# 780-00020_rev_2_pg1_Two_Axis_Stepper_Dri.net
KiCad netlist of a schematic drawn in Altium Designer
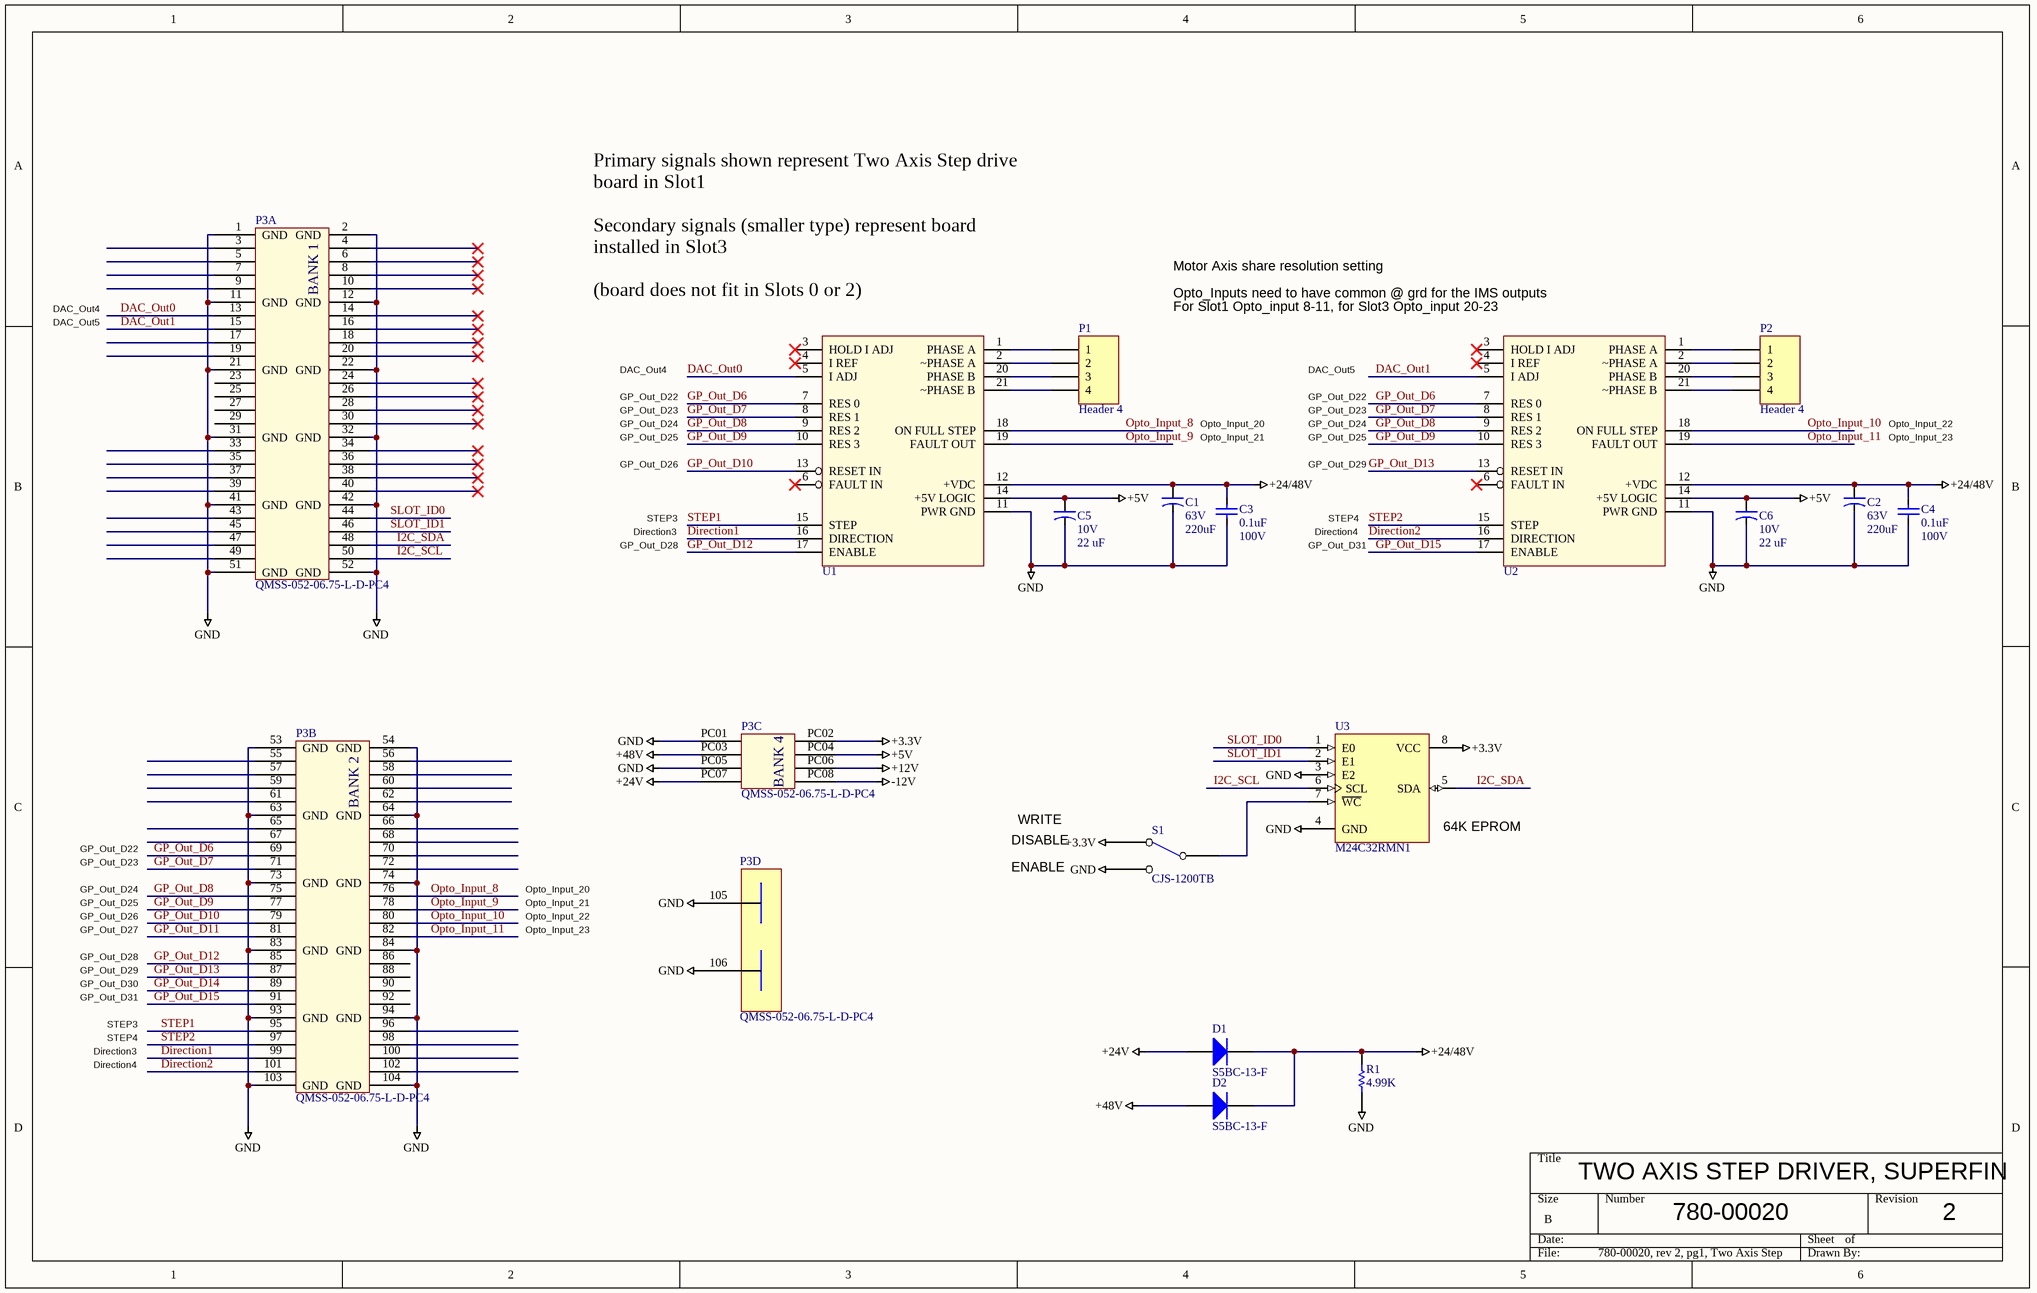
[diagram p0: 780-00020, rev 2, pg1, Two Axis Stepper Driver.SchDoc]

(export (version "E")
  (design (tool "Eeschema 10.0.6"))
  (components
    (comp (ref "C1")
      (value "63V")
      (footprint "CAP 220uF 63V")
      (description "CAP 220UF 63V ELECT MVH SMD")
      (fields (field (name "MANUFACTURER") "United Chemi-Con") (field (name "ALTIUM_VALUE") "220uF"))
      (libsource (lib "Richs Schematic Components") (part "Cap 220uF, 63V"))
    )
    (comp (ref "C2")
      (value "63V")
      (footprint "CAP 220uF 63V")
      (description "CAP 220UF 63V ELECT MVH SMD")
      (fields (field (name "MANUFACTURER") "United Chemi-Con") (field (name "ALTIUM_VALUE") "220uF"))
      (libsource (lib "Richs Schematic Components") (part "Cap 220uF, 63V"))
    )
    (comp (ref "C3")
      (value "100V")
      (footprint "SMD_0805")
      (description "Capacitor")
      (fields (field (name "MANUFACTURER") "TDK") (field (name "ALTIUM_VALUE") "0.1uF"))
      (libsource (lib "Richs Schematic Components") (part "Cap SMD"))
    )
    (comp (ref "C4")
      (value "100V")
      (footprint "SMD_0805")
      (description "Capacitor")
      (fields (field (name "MANUFACTURER") "TDK") (field (name "ALTIUM_VALUE") "0.1uF"))
      (libsource (lib "Richs Schematic Components") (part "Cap SMD"))
    )
    (comp (ref "C5")
      (value "10V")
      (footprint "SMD_CAP_3216")
      (description "outline 3.2mm x 1.6mm")
      (fields (field (name "MANUFACTURER") "AVX") (field (name "ALTIUM_VALUE") "22 uF"))
      (libsource (lib "Richs Schematic Components") (part "Cap Tant 16V"))
    )
    (comp (ref "C6")
      (value "10V")
      (footprint "SMD_CAP_3216")
      (description "outline 3.2mm x 1.6mm")
      (fields (field (name "MANUFACTURER") "AVX") (field (name "ALTIUM_VALUE") "22 uF"))
      (libsource (lib "Richs Schematic Components") (part "Cap Tant 16V"))
    )
    (comp (ref "D1")
      (value "S5BC-13-F")
      (footprint "SMC")
      (description "RECTIFIER GPP SMD 100V 5A SMC")
      (fields (field (name "MANUFACTURER") "Diodes Inc"))
      (libsource (lib "Miscellaneous Devices") (part "Diode"))
    )
    (comp (ref "D2")
      (value "S5BC-13-F")
      (footprint "SMC")
      (description "RECTIFIER GPP SMD 100V 5A SMC")
      (fields (field (name "MANUFACTURER") "Diodes Inc"))
      (libsource (lib "Miscellaneous Devices") (part "Diode"))
    )
    (comp (ref "P1")
      (value "Header 4")
      (footprint "HDR1X4 for IDC")
      (description "Header, 4-Pin")
      (libsource (lib "Richs Schematic Components") (part "Header 4"))
    )
    (comp (ref "P2")
      (value "Header 4")
      (footprint "HDR1X4 for IDC")
      (description "Header, 4-Pin")
      (libsource (lib "Richs Schematic Components") (part "Header 4"))
    )
    (comp (ref "P3")
      (value "QMSS-052-06.75-L-D-PC4")
      (footprint "QMS SMD PWR PINS - 104PIN")
      (description "SAMTEC QMSS W/PWR PINS")
      (fields (field (name "MANUFACTURER") "SAMTEC"))
      (libsource (lib "Richs Schematic Components") (part "QMSS-PC4-104 pin"))
    )
    (comp (ref "R1")
      (value "4.99K")
      (footprint "SMD_0805")
      (description "Resistor 0805")
      (fields (field (name "MANUFACTURER") "Vishay/Dale") (field (name "Comment") "Res 0805"))
      (libsource (lib "Richs Schematic Components") (part "Res SMD"))
    )
    (comp (ref "S1")
      (value "CJS-1200TB")
      (footprint "CAS-120B")
      (fields (field (name "MANUFACTURER") "Copal Electronics"))
      (libsource (lib "JON_1_Library") (part "SW_SPDT_DOUG"))
    )
    (comp (ref "U1")
      (value "IM481H Plus")
      (footprint "IM481H Vertical")
      (description "Hybrid stepper motor driver")
      (libsource (lib "Richs Schematic Components") (part "IM481H Plus"))
    )
    (comp (ref "U2")
      (value "IM481H Plus")
      (footprint "IM481H Vertical")
      (description "Hybrid stepper motor driver")
      (libsource (lib "Richs Schematic Components") (part "IM481H Plus"))
    )
    (comp (ref "U3")
      (value "M24C32RMN1")
      (footprint "SOP8_N")
      (description "32 Kbit Serial I²C Bus EEPROM")
      (libsource (lib "ST Memory EEPROM Serial") (part "M24C32RMN1"))
    )
  )
  (nets
    (net (code "1") (name "+3.3V") (class "Default")
      (node (ref "P3") (pin "PC02") (pinfunction "PC02_PC02") (pintype "passive"))
      (node (ref "S1") (pin "3") (pinfunction "NC_3") (pintype "passive"))
      (node (ref "U3") (pin "8") (pinfunction "VCC_8") (pintype "power_in"))
    )
    (net (code "2") (name "+5V") (class "Default")
      (node (ref "C5") (pin "1") (pinfunction "1_1") (pintype "passive"))
      (node (ref "C6") (pin "1") (pinfunction "1_1") (pintype "passive"))
      (node (ref "P3") (pin "PC04") (pinfunction "PC04_PC04") (pintype "passive"))
      (node (ref "U1") (pin "14") (pinfunction "+5V_LOGIC_14") (pintype "passive"))
      (node (ref "U2") (pin "14") (pinfunction "+5V_LOGIC_14") (pintype "passive"))
    )
    (net (code "3") (name "+12V") (class "Default")
      (node (ref "P3") (pin "PC06") (pinfunction "PC06_PC06") (pintype "passive"))
    )
    (net (code "4") (name "+24V") (class "Default")
      (node (ref "D1") (pin "1") (pinfunction "A_1") (pintype "passive"))
      (node (ref "P3") (pin "PC07") (pinfunction "PC07_PC07") (pintype "passive"))
    )
    (net (code "5") (name "+24{slash}48V") (class "Default")
      (node (ref "C1") (pin "1") (pinfunction "1_1") (pintype "passive"))
      (node (ref "C2") (pin "1") (pinfunction "1_1") (pintype "passive"))
      (node (ref "C3") (pin "2") (pinfunction "2_2") (pintype "passive"))
      (node (ref "C4") (pin "2") (pinfunction "2_2") (pintype "passive"))
      (node (ref "D1") (pin "2") (pinfunction "K_2") (pintype "passive"))
      (node (ref "D2") (pin "2") (pinfunction "K_2") (pintype "passive"))
      (node (ref "R1") (pin "2") (pinfunction "2_2") (pintype "passive"))
      (node (ref "U1") (pin "12") (pinfunction "+VDC_12") (pintype "passive"))
      (node (ref "U2") (pin "12") (pinfunction "+VDC_12") (pintype "passive"))
    )
    (net (code "6") (name "+48V") (class "Default")
      (node (ref "D2") (pin "1") (pinfunction "A_1") (pintype "passive"))
      (node (ref "P3") (pin "PC03") (pinfunction "PC03_PC03") (pintype "passive"))
    )
    (net (code "7") (name "-12V") (class "Default")
      (node (ref "P3") (pin "PC08") (pinfunction "PC08_PC08") (pintype "passive"))
    )
    (net (code "8") (name "/DAC_Out0") (class "Default")
      (node (ref "P3") (pin "13") (pinfunction "13_13") (pintype "passive"))
      (node (ref "U1") (pin "5") (pinfunction "I_ADJ_5") (pintype "passive"))
    )
    (net (code "9") (name "/DAC_Out1") (class "Default")
      (node (ref "P3") (pin "15") (pinfunction "15_15") (pintype "passive"))
      (node (ref "U2") (pin "5") (pinfunction "I_ADJ_5") (pintype "passive"))
    )
    (net (code "10") (name "/Direction1") (class "Default")
      (node (ref "P3") (pin "99") (pinfunction "99_99") (pintype "passive"))
      (node (ref "U1") (pin "16") (pinfunction "DIRECTION_16") (pintype "passive"))
    )
    (net (code "11") (name "/Direction2") (class "Default")
      (node (ref "P3") (pin "101") (pinfunction "101_101") (pintype "passive"))
      (node (ref "U2") (pin "16") (pinfunction "DIRECTION_16") (pintype "passive"))
    )
    (net (code "12") (name "/GP_Out_D6") (class "Default")
      (node (ref "P3") (pin "69") (pinfunction "69_69") (pintype "passive"))
      (node (ref "U1") (pin "7") (pinfunction "RES_0_7") (pintype "passive"))
      (node (ref "U2") (pin "7") (pinfunction "RES_0_7") (pintype "passive"))
    )
    (net (code "13") (name "/GP_Out_D7") (class "Default")
      (node (ref "P3") (pin "71") (pinfunction "71_71") (pintype "passive"))
      (node (ref "U1") (pin "8") (pinfunction "RES_1_8") (pintype "passive"))
      (node (ref "U2") (pin "8") (pinfunction "RES_1_8") (pintype "passive"))
    )
    (net (code "14") (name "/GP_Out_D8") (class "Default")
      (node (ref "P3") (pin "75") (pinfunction "75_75") (pintype "passive"))
      (node (ref "U1") (pin "9") (pinfunction "RES_2_9") (pintype "passive"))
      (node (ref "U2") (pin "9") (pinfunction "RES_2_9") (pintype "passive"))
    )
    (net (code "15") (name "/GP_Out_D9") (class "Default")
      (node (ref "P3") (pin "77") (pinfunction "77_77") (pintype "passive"))
      (node (ref "U1") (pin "10") (pinfunction "RES_3_10") (pintype "passive"))
      (node (ref "U2") (pin "10") (pinfunction "RES_3_10") (pintype "passive"))
    )
    (net (code "16") (name "/GP_Out_D10") (class "Default")
      (node (ref "P3") (pin "79") (pinfunction "79_79") (pintype "passive"))
      (node (ref "U1") (pin "13") (pinfunction "RESET_IN_13") (pintype "passive"))
    )
    (net (code "17") (name "/GP_Out_D11") (class "Default")
      (node (ref "P3") (pin "81") (pinfunction "81_81") (pintype "passive"))
    )
    (net (code "18") (name "/GP_Out_D12") (class "Default")
      (node (ref "P3") (pin "85") (pinfunction "85_85") (pintype "passive"))
      (node (ref "U1") (pin "17") (pinfunction "ENABLE_17") (pintype "passive"))
    )
    (net (code "19") (name "/GP_Out_D13") (class "Default")
      (node (ref "P3") (pin "87") (pinfunction "87_87") (pintype "passive"))
      (node (ref "U2") (pin "13") (pinfunction "RESET_IN_13") (pintype "passive"))
    )
    (net (code "20") (name "/GP_Out_D14") (class "Default")
      (node (ref "P3") (pin "89") (pinfunction "89_89") (pintype "passive"))
    )
    (net (code "21") (name "/GP_Out_D15") (class "Default")
      (node (ref "P3") (pin "91") (pinfunction "91_91") (pintype "passive"))
      (node (ref "U2") (pin "17") (pinfunction "ENABLE_17") (pintype "passive"))
    )
    (net (code "22") (name "/I2C_SCL") (class "Default")
      (node (ref "P3") (pin "50") (pinfunction "50_50") (pintype "passive"))
      (node (ref "U3") (pin "6") (pinfunction "SCL_6") (pintype "input"))
    )
    (net (code "23") (name "/I2C_SDA") (class "Default")
      (node (ref "P3") (pin "48") (pinfunction "48_48") (pintype "passive"))
      (node (ref "U3") (pin "5") (pinfunction "SDA_5") (pintype "bidirectional"))
    )
    (net (code "24") (name "/Opto_Input_8") (class "Default")
      (node (ref "P3") (pin "76") (pinfunction "76_76") (pintype "passive"))
      (node (ref "U1") (pin "18") (pinfunction "ON_FULL_STEP_18") (pintype "passive"))
    )
    (net (code "25") (name "/Opto_Input_9") (class "Default")
      (node (ref "P3") (pin "78") (pinfunction "78_78") (pintype "passive"))
      (node (ref "U1") (pin "19") (pinfunction "FAULT_OUT_19") (pintype "passive"))
    )
    (net (code "26") (name "/Opto_Input_10") (class "Default")
      (node (ref "P3") (pin "80") (pinfunction "80_80") (pintype "passive"))
      (node (ref "U2") (pin "18") (pinfunction "ON_FULL_STEP_18") (pintype "passive"))
    )
    (net (code "27") (name "/Opto_Input_11") (class "Default")
      (node (ref "P3") (pin "82") (pinfunction "82_82") (pintype "passive"))
      (node (ref "U2") (pin "19") (pinfunction "FAULT_OUT_19") (pintype "passive"))
    )
    (net (code "28") (name "/SLOT_ID0") (class "Default")
      (node (ref "P3") (pin "44") (pinfunction "44_44") (pintype "passive"))
      (node (ref "U3") (pin "1") (pinfunction "E0_1") (pintype "input"))
    )
    (net (code "29") (name "/SLOT_ID1") (class "Default")
      (node (ref "P3") (pin "46") (pinfunction "46_46") (pintype "passive"))
      (node (ref "U3") (pin "2") (pinfunction "E1_2") (pintype "input"))
    )
    (net (code "30") (name "/STEP1") (class "Default")
      (node (ref "P3") (pin "95") (pinfunction "95_95") (pintype "passive"))
      (node (ref "U1") (pin "15") (pinfunction "STEP_15") (pintype "passive"))
    )
    (net (code "31") (name "/STEP2") (class "Default")
      (node (ref "P3") (pin "97") (pinfunction "97_97") (pintype "passive"))
      (node (ref "U2") (pin "15") (pinfunction "STEP_15") (pintype "passive"))
    )
    (net (code "32") (name "GND") (class "Default")
      (node (ref "C1") (pin "2") (pinfunction "2_2") (pintype "passive"))
      (node (ref "C2") (pin "2") (pinfunction "2_2") (pintype "passive"))
      (node (ref "C3") (pin "1") (pinfunction "1_1") (pintype "passive"))
      (node (ref "C4") (pin "1") (pinfunction "1_1") (pintype "passive"))
      (node (ref "C5") (pin "2") (pinfunction "2_2") (pintype "passive"))
      (node (ref "C6") (pin "2") (pinfunction "2_2") (pintype "passive"))
      (node (ref "P3") (pin "1") (pinfunction "GND_1") (pintype "passive"))
      (node (ref "P3") (pin "103") (pinfunction "GND_103") (pintype "passive"))
      (node (ref "P3") (pin "104") (pinfunction "GND_104") (pintype "passive"))
      (node (ref "P3") (pin "105") (pinfunction "GND_105") (pintype "passive"))
      (node (ref "P3") (pin "106") (pinfunction "GND_106") (pintype "passive"))
      (node (ref "P3") (pin "11") (pinfunction "GND_11") (pintype "passive"))
      (node (ref "P3") (pin "12") (pinfunction "GND_12") (pintype "passive"))
      (node (ref "P3") (pin "2") (pinfunction "GND_2") (pintype "passive"))
      (node (ref "P3") (pin "21") (pinfunction "GND_21") (pintype "passive"))
      (node (ref "P3") (pin "22") (pinfunction "GND_22") (pintype "passive"))
      (node (ref "P3") (pin "31") (pinfunction "GND_31") (pintype "passive"))
      (node (ref "P3") (pin "32") (pinfunction "GND_32") (pintype "passive"))
      (node (ref "P3") (pin "41") (pinfunction "GND_41") (pintype "passive"))
      (node (ref "P3") (pin "42") (pinfunction "GND_42") (pintype "passive"))
      (node (ref "P3") (pin "51") (pinfunction "GND_51") (pintype "passive"))
      (node (ref "P3") (pin "52") (pinfunction "GND_52") (pintype "passive"))
      (node (ref "P3") (pin "53") (pinfunction "GND_53") (pintype "passive"))
      (node (ref "P3") (pin "54") (pinfunction "GND_54") (pintype "passive"))
      (node (ref "P3") (pin "63") (pinfunction "GND_63") (pintype "passive"))
      (node (ref "P3") (pin "64") (pinfunction "GND_64") (pintype "passive"))
      (node (ref "P3") (pin "73") (pinfunction "GND_73") (pintype "passive"))
      (node (ref "P3") (pin "74") (pinfunction "GND_74") (pintype "passive"))
      (node (ref "P3") (pin "83") (pinfunction "GND_83") (pintype "passive"))
      (node (ref "P3") (pin "84") (pinfunction "GND_84") (pintype "passive"))
      (node (ref "P3") (pin "93") (pinfunction "GND_93") (pintype "passive"))
      (node (ref "P3") (pin "94") (pinfunction "GND_94") (pintype "passive"))
      (node (ref "P3") (pin "PC01") (pinfunction "PC01_PC01") (pintype "passive"))
      (node (ref "P3") (pin "PC05") (pinfunction "PC05_PC05") (pintype "passive"))
      (node (ref "R1") (pin "1") (pinfunction "1_1") (pintype "passive"))
      (node (ref "S1") (pin "1") (pinfunction "NO_1") (pintype "passive"))
      (node (ref "U1") (pin "11") (pinfunction "PWR_GND_11") (pintype "passive"))
      (node (ref "U2") (pin "11") (pinfunction "PWR_GND_11") (pintype "passive"))
      (node (ref "U3") (pin "3") (pinfunction "E2_3") (pintype "input"))
      (node (ref "U3") (pin "4") (pinfunction "GND_4") (pintype "power_in"))
    )
    (net (code "33") (name "Net-(S1-COM)") (class "Default")
      (node (ref "S1") (pin "2") (pinfunction "COM_2") (pintype "passive"))
      (node (ref "U3") (pin "7") (pinfunction "~{WC}_7") (pintype "input"))
    )
    (net (code "34") (name "Net-(U1-PHASE_A)") (class "Default")
      (node (ref "P1") (pin "1") (pinfunction "1_1") (pintype "passive"))
      (node (ref "U1") (pin "1") (pinfunction "PHASE_A_1") (pintype "passive"))
    )
    (net (code "35") (name "Net-(U1-PHASE_B)") (class "Default")
      (node (ref "P1") (pin "3") (pinfunction "3_3") (pintype "passive"))
      (node (ref "U1") (pin "20") (pinfunction "PHASE_B_20") (pintype "passive"))
    )
    (net (code "36") (name "Net-(U1-~PHASE_A)") (class "Default")
      (node (ref "P1") (pin "2") (pinfunction "2_2") (pintype "passive"))
      (node (ref "U1") (pin "2") (pinfunction "~PHASE_A_2") (pintype "passive"))
    )
    (net (code "37") (name "Net-(U1-~PHASE_B)") (class "Default")
      (node (ref "P1") (pin "4") (pinfunction "4_4") (pintype "passive"))
      (node (ref "U1") (pin "21") (pinfunction "~PHASE_B_21") (pintype "passive"))
    )
    (net (code "38") (name "Net-(U2-PHASE_A)") (class "Default")
      (node (ref "P2") (pin "1") (pinfunction "1_1") (pintype "passive"))
      (node (ref "U2") (pin "1") (pinfunction "PHASE_A_1") (pintype "passive"))
    )
    (net (code "39") (name "Net-(U2-PHASE_B)") (class "Default")
      (node (ref "P2") (pin "3") (pinfunction "3_3") (pintype "passive"))
      (node (ref "U2") (pin "20") (pinfunction "PHASE_B_20") (pintype "passive"))
    )
    (net (code "40") (name "Net-(U2-~PHASE_A)") (class "Default")
      (node (ref "P2") (pin "2") (pinfunction "2_2") (pintype "passive"))
      (node (ref "U2") (pin "2") (pinfunction "~PHASE_A_2") (pintype "passive"))
    )
    (net (code "41") (name "Net-(U2-~PHASE_B)") (class "Default")
      (node (ref "P2") (pin "4") (pinfunction "4_4") (pintype "passive"))
      (node (ref "U2") (pin "21") (pinfunction "~PHASE_B_21") (pintype "passive"))
    )
    (net (code "42") (name "unconnected-(P3-Pad3)") (class "Default")
      (node (ref "P3") (pin "3") (pinfunction "3_3") (pintype "passive"))
    )
    (net (code "43") (name "unconnected-(P3-Pad4)") (class "Default")
      (node (ref "P3") (pin "4") (pinfunction "4_4") (pintype "passive+no_connect"))
    )
    (net (code "44") (name "unconnected-(P3-Pad5)") (class "Default")
      (node (ref "P3") (pin "5") (pinfunction "5_5") (pintype "passive"))
    )
    (net (code "45") (name "unconnected-(P3-Pad6)") (class "Default")
      (node (ref "P3") (pin "6") (pinfunction "6_6") (pintype "passive+no_connect"))
    )
    (net (code "46") (name "unconnected-(P3-Pad7)") (class "Default")
      (node (ref "P3") (pin "7") (pinfunction "7_7") (pintype "passive"))
    )
    (net (code "47") (name "unconnected-(P3-Pad8)") (class "Default")
      (node (ref "P3") (pin "8") (pinfunction "8_8") (pintype "passive+no_connect"))
    )
    (net (code "48") (name "unconnected-(P3-Pad9)") (class "Default")
      (node (ref "P3") (pin "9") (pinfunction "9_9") (pintype "passive"))
    )
    (net (code "49") (name "unconnected-(P3-Pad10)") (class "Default")
      (node (ref "P3") (pin "10") (pinfunction "10_10") (pintype "passive+no_connect"))
    )
    (net (code "50") (name "unconnected-(P3-Pad14)") (class "Default")
      (node (ref "P3") (pin "14") (pinfunction "14_14") (pintype "passive+no_connect"))
    )
    (net (code "51") (name "unconnected-(P3-Pad16)") (class "Default")
      (node (ref "P3") (pin "16") (pinfunction "16_16") (pintype "passive+no_connect"))
    )
    (net (code "52") (name "unconnected-(P3-Pad17)") (class "Default")
      (node (ref "P3") (pin "17") (pinfunction "17_17") (pintype "passive"))
    )
    (net (code "53") (name "unconnected-(P3-Pad18)") (class "Default")
      (node (ref "P3") (pin "18") (pinfunction "18_18") (pintype "passive+no_connect"))
    )
    (net (code "54") (name "unconnected-(P3-Pad19)") (class "Default")
      (node (ref "P3") (pin "19") (pinfunction "19_19") (pintype "passive"))
    )
    (net (code "55") (name "unconnected-(P3-Pad20)") (class "Default")
      (node (ref "P3") (pin "20") (pinfunction "20_20") (pintype "passive+no_connect"))
    )
    (net (code "56") (name "unconnected-(P3-Pad23)") (class "Default")
      (node (ref "P3") (pin "23") (pinfunction "23_23") (pintype "passive"))
    )
    (net (code "57") (name "unconnected-(P3-Pad24)") (class "Default")
      (node (ref "P3") (pin "24") (pinfunction "24_24") (pintype "passive+no_connect"))
    )
    (net (code "58") (name "unconnected-(P3-Pad25)") (class "Default")
      (node (ref "P3") (pin "25") (pinfunction "25_25") (pintype "passive"))
    )
    (net (code "59") (name "unconnected-(P3-Pad26)") (class "Default")
      (node (ref "P3") (pin "26") (pinfunction "26_26") (pintype "passive+no_connect"))
    )
    (net (code "60") (name "unconnected-(P3-Pad27)") (class "Default")
      (node (ref "P3") (pin "27") (pinfunction "27_27") (pintype "passive"))
    )
    (net (code "61") (name "unconnected-(P3-Pad28)") (class "Default")
      (node (ref "P3") (pin "28") (pinfunction "28_28") (pintype "passive+no_connect"))
    )
    (net (code "62") (name "unconnected-(P3-Pad29)") (class "Default")
      (node (ref "P3") (pin "29") (pinfunction "29_29") (pintype "passive"))
    )
    (net (code "63") (name "unconnected-(P3-Pad30)") (class "Default")
      (node (ref "P3") (pin "30") (pinfunction "30_30") (pintype "passive+no_connect"))
    )
    (net (code "64") (name "unconnected-(P3-Pad33)") (class "Default")
      (node (ref "P3") (pin "33") (pinfunction "33_33") (pintype "passive"))
    )
    (net (code "65") (name "unconnected-(P3-Pad34)") (class "Default")
      (node (ref "P3") (pin "34") (pinfunction "34_34") (pintype "passive+no_connect"))
    )
    (net (code "66") (name "unconnected-(P3-Pad35)") (class "Default")
      (node (ref "P3") (pin "35") (pinfunction "35_35") (pintype "passive"))
    )
    (net (code "67") (name "unconnected-(P3-Pad36)") (class "Default")
      (node (ref "P3") (pin "36") (pinfunction "36_36") (pintype "passive+no_connect"))
    )
    (net (code "68") (name "unconnected-(P3-Pad37)") (class "Default")
      (node (ref "P3") (pin "37") (pinfunction "37_37") (pintype "passive"))
    )
    (net (code "69") (name "unconnected-(P3-Pad38)") (class "Default")
      (node (ref "P3") (pin "38") (pinfunction "38_38") (pintype "passive+no_connect"))
    )
    (net (code "70") (name "unconnected-(P3-Pad39)") (class "Default")
      (node (ref "P3") (pin "39") (pinfunction "39_39") (pintype "passive"))
    )
    (net (code "71") (name "unconnected-(P3-Pad40)") (class "Default")
      (node (ref "P3") (pin "40") (pinfunction "40_40") (pintype "passive+no_connect"))
    )
    (net (code "72") (name "unconnected-(P3-Pad43)") (class "Default")
      (node (ref "P3") (pin "43") (pinfunction "43_43") (pintype "passive"))
    )
    (net (code "73") (name "unconnected-(P3-Pad45)") (class "Default")
      (node (ref "P3") (pin "45") (pinfunction "45_45") (pintype "passive"))
    )
    (net (code "74") (name "unconnected-(P3-Pad47)") (class "Default")
      (node (ref "P3") (pin "47") (pinfunction "47_47") (pintype "passive"))
    )
    (net (code "75") (name "unconnected-(P3-Pad49)") (class "Default")
      (node (ref "P3") (pin "49") (pinfunction "49_49") (pintype "passive"))
    )
    (net (code "76") (name "unconnected-(P3-Pad55)") (class "Default")
      (node (ref "P3") (pin "55") (pinfunction "55_55") (pintype "passive"))
    )
    (net (code "77") (name "unconnected-(P3-Pad56)") (class "Default")
      (node (ref "P3") (pin "56") (pinfunction "56_56") (pintype "passive"))
    )
    (net (code "78") (name "unconnected-(P3-Pad57)") (class "Default")
      (node (ref "P3") (pin "57") (pinfunction "57_57") (pintype "passive"))
    )
    (net (code "79") (name "unconnected-(P3-Pad58)") (class "Default")
      (node (ref "P3") (pin "58") (pinfunction "58_58") (pintype "passive"))
    )
    (net (code "80") (name "unconnected-(P3-Pad59)") (class "Default")
      (node (ref "P3") (pin "59") (pinfunction "59_59") (pintype "passive"))
    )
    (net (code "81") (name "unconnected-(P3-Pad60)") (class "Default")
      (node (ref "P3") (pin "60") (pinfunction "60_60") (pintype "passive"))
    )
    (net (code "82") (name "unconnected-(P3-Pad61)") (class "Default")
      (node (ref "P3") (pin "61") (pinfunction "61_61") (pintype "passive"))
    )
    (net (code "83") (name "unconnected-(P3-Pad62)") (class "Default")
      (node (ref "P3") (pin "62") (pinfunction "62_62") (pintype "passive"))
    )
    (net (code "84") (name "unconnected-(P3-Pad65)") (class "Default")
      (node (ref "P3") (pin "65") (pinfunction "65_65") (pintype "passive"))
    )
    (net (code "85") (name "unconnected-(P3-Pad66)") (class "Default")
      (node (ref "P3") (pin "66") (pinfunction "66_66") (pintype "passive"))
    )
    (net (code "86") (name "unconnected-(P3-Pad67)") (class "Default")
      (node (ref "P3") (pin "67") (pinfunction "67_67") (pintype "passive"))
    )
    (net (code "87") (name "unconnected-(P3-Pad68)") (class "Default")
      (node (ref "P3") (pin "68") (pinfunction "68_68") (pintype "passive"))
    )
    (net (code "88") (name "unconnected-(P3-Pad70)") (class "Default")
      (node (ref "P3") (pin "70") (pinfunction "70_70") (pintype "passive"))
    )
    (net (code "89") (name "unconnected-(P3-Pad72)") (class "Default")
      (node (ref "P3") (pin "72") (pinfunction "72_72") (pintype "passive"))
    )
    (net (code "90") (name "unconnected-(P3-Pad86)") (class "Default")
      (node (ref "P3") (pin "86") (pinfunction "86_86") (pintype "passive"))
    )
    (net (code "91") (name "unconnected-(P3-Pad88)") (class "Default")
      (node (ref "P3") (pin "88") (pinfunction "88_88") (pintype "passive"))
    )
    (net (code "92") (name "unconnected-(P3-Pad90)") (class "Default")
      (node (ref "P3") (pin "90") (pinfunction "90_90") (pintype "passive"))
    )
    (net (code "93") (name "unconnected-(P3-Pad92)") (class "Default")
      (node (ref "P3") (pin "92") (pinfunction "92_92") (pintype "passive"))
    )
    (net (code "94") (name "unconnected-(P3-Pad96)") (class "Default")
      (node (ref "P3") (pin "96") (pinfunction "96_96") (pintype "passive"))
    )
    (net (code "95") (name "unconnected-(P3-Pad98)") (class "Default")
      (node (ref "P3") (pin "98") (pinfunction "98_98") (pintype "passive"))
    )
    (net (code "96") (name "unconnected-(P3-Pad100)") (class "Default")
      (node (ref "P3") (pin "100") (pinfunction "100_100") (pintype "passive"))
    )
    (net (code "97") (name "unconnected-(P3-Pad102)") (class "Default")
      (node (ref "P3") (pin "102") (pinfunction "102_102") (pintype "passive"))
    )
    (net (code "98") (name "unconnected-(U1-FAULT_IN-Pad6)") (class "Default")
      (node (ref "U1") (pin "6") (pinfunction "FAULT_IN_6") (pintype "passive+no_connect"))
    )
    (net (code "99") (name "unconnected-(U1-HOLD_I_ADJ-Pad3)") (class "Default")
      (node (ref "U1") (pin "3") (pinfunction "HOLD_I_ADJ_3") (pintype "passive+no_connect"))
    )
    (net (code "100") (name "unconnected-(U1-I_REF-Pad4)") (class "Default")
      (node (ref "U1") (pin "4") (pinfunction "I_REF_4") (pintype "passive+no_connect"))
    )
    (net (code "101") (name "unconnected-(U2-FAULT_IN-Pad6)") (class "Default")
      (node (ref "U2") (pin "6") (pinfunction "FAULT_IN_6") (pintype "passive+no_connect"))
    )
    (net (code "102") (name "unconnected-(U2-HOLD_I_ADJ-Pad3)") (class "Default")
      (node (ref "U2") (pin "3") (pinfunction "HOLD_I_ADJ_3") (pintype "passive+no_connect"))
    )
    (net (code "103") (name "unconnected-(U2-I_REF-Pad4)") (class "Default")
      (node (ref "U2") (pin "4") (pinfunction "I_REF_4") (pintype "passive+no_connect"))
    )
  )
)
